# 7segdmux.net
KiCad netlist of a schematic drawn in EAGLE
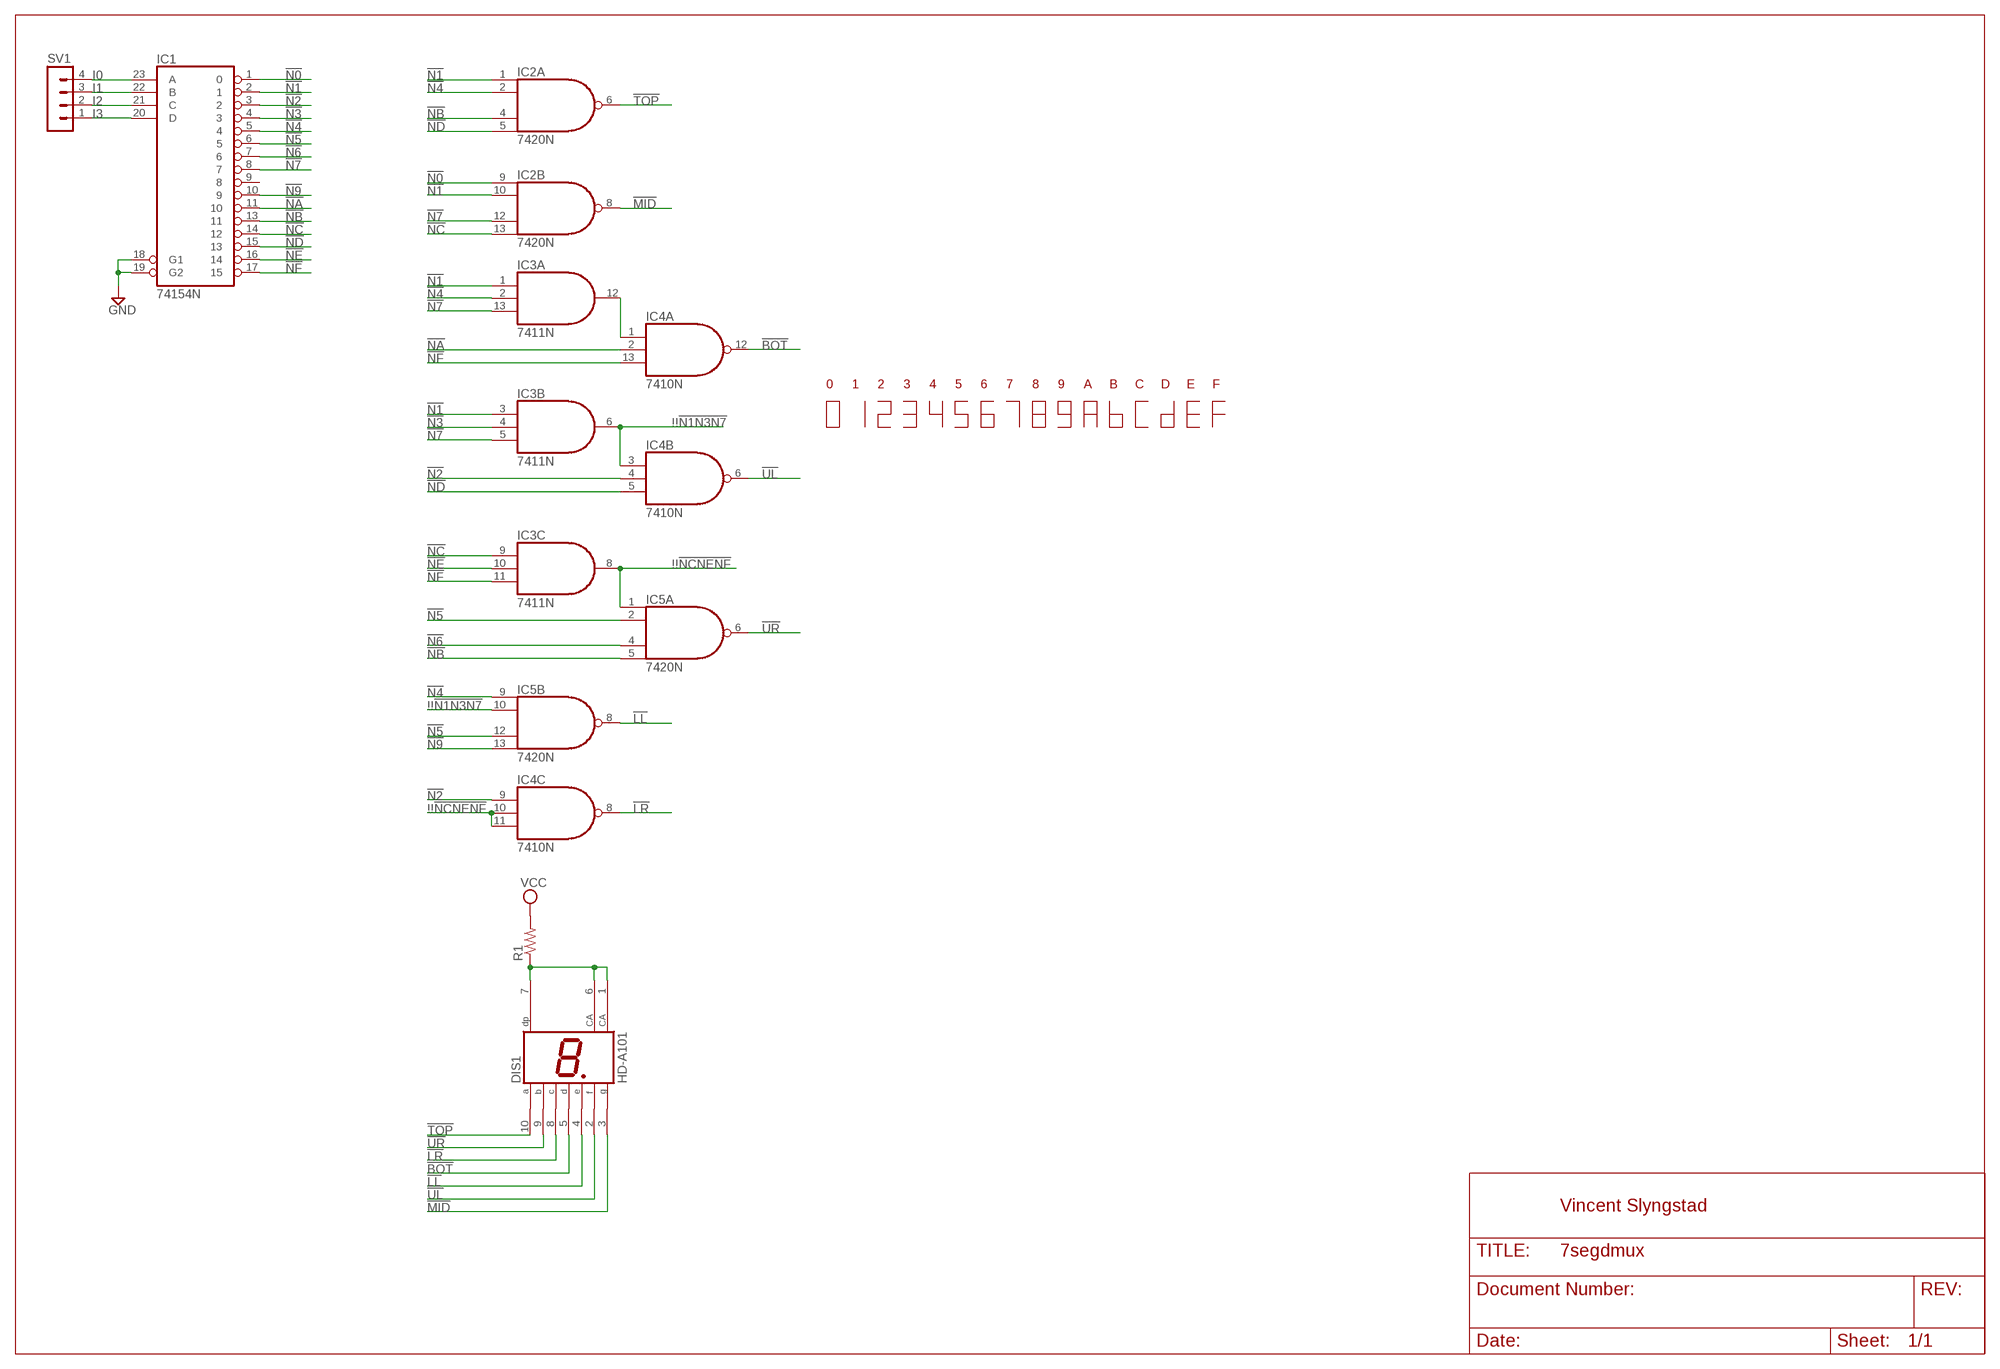
[diagram p0: schematic, sheet 1]

(export (version "E")
  (design (tool "Eeschema 10.0.6"))
  (components
    (comp (ref "DIS1")
      (value "HD-A101")
      (footprint "eagle-import:HDSP-A")
      (libsource (lib "eagle-import") (part "HD-A101"))
    )
    (comp (ref "IC1")
      (value "74154N")
      (footprint "eagle-import:DIL24-6")
      (libsource (lib "eagle-import") (part "74154N"))
    )
    (comp (ref "IC2")
      (value "7420N")
      (footprint "eagle-import:DIL14")
      (libsource (lib "eagle-import") (part "7420NS"))
    )
    (comp (ref "IC3")
      (value "7411N")
      (footprint "eagle-import:DIL14")
      (libsource (lib "eagle-import") (part "7411NS"))
    )
    (comp (ref "IC4")
      (value "7410N")
      (footprint "eagle-import:DIL14")
      (libsource (lib "eagle-import") (part "7410N"))
    )
    (comp (ref "IC5")
      (value "7420N")
      (footprint "eagle-import:DIL14")
      (libsource (lib "eagle-import") (part "7420NS"))
    )
    (comp (ref "R1")
      (value "R-US_0207/10")
      (footprint "eagle-import:0207_10")
      (libsource (lib "eagle-import") (part "R-US_0207/10"))
    )
    (comp (ref "SV1")
      (value "MA04-1")
      (footprint "eagle-import:MA04-1")
      (libsource (lib "eagle-import") (part "MA04-1"))
    )
  )
  (nets
    (net (code "1") (name "/I0") (class "Default")
      (node (ref "IC1") (pin "23") (pinfunction "A_23") (pintype "input"))
      (node (ref "SV1") (pin "4") (pinfunction "4_4") (pintype "passive"))
    )
    (net (code "2") (name "/I1") (class "Default")
      (node (ref "IC1") (pin "22") (pinfunction "B_22") (pintype "input"))
      (node (ref "SV1") (pin "3") (pinfunction "3_3") (pintype "passive"))
    )
    (net (code "3") (name "/I2") (class "Default")
      (node (ref "IC1") (pin "21") (pinfunction "C_21") (pintype "input"))
      (node (ref "SV1") (pin "2") (pinfunction "2_2") (pintype "passive"))
    )
    (net (code "4") (name "/I3") (class "Default")
      (node (ref "IC1") (pin "20") (pinfunction "D_20") (pintype "input"))
      (node (ref "SV1") (pin "1") (pinfunction "1_1") (pintype "passive"))
    )
    (net (code "5") (name "/~{BOT}") (class "Default")
      (node (ref "DIS1") (pin "5") (pinfunction "D_5") (pintype "passive"))
      (node (ref "IC4") (pin "12") (pinfunction "O_12") (pintype "output"))
    )
    (net (code "6") (name "/~{LL}") (class "Default")
      (node (ref "DIS1") (pin "4") (pinfunction "E_4") (pintype "passive"))
      (node (ref "IC5") (pin "8") (pinfunction "O_8") (pintype "output"))
    )
    (net (code "7") (name "/~{LR}") (class "Default")
      (node (ref "DIS1") (pin "8") (pinfunction "C_8") (pintype "passive"))
      (node (ref "IC4") (pin "8") (pinfunction "O_8") (pintype "output"))
    )
    (net (code "8") (name "/~{MID}") (class "Default")
      (node (ref "DIS1") (pin "3") (pinfunction "G_3") (pintype "passive"))
      (node (ref "IC2") (pin "8") (pinfunction "O_8") (pintype "output"))
    )
    (net (code "9") (name "/~{N0}") (class "Default")
      (node (ref "IC1") (pin "1") (pinfunction "0_1") (pintype "output"))
      (node (ref "IC2") (pin "9") (pinfunction "I0_9") (pintype "input"))
    )
    (net (code "10") (name "/~{N1}") (class "Default")
      (node (ref "IC1") (pin "2") (pinfunction "1_2") (pintype "output"))
      (node (ref "IC2") (pin "1") (pinfunction "I0_1") (pintype "input"))
      (node (ref "IC2") (pin "10") (pinfunction "I1_10") (pintype "input"))
      (node (ref "IC3") (pin "1") (pinfunction "I0_1") (pintype "input"))
      (node (ref "IC3") (pin "3") (pinfunction "I0_3") (pintype "input"))
    )
    (net (code "11") (name "/~{N2}") (class "Default")
      (node (ref "IC1") (pin "3") (pinfunction "2_3") (pintype "output"))
      (node (ref "IC4") (pin "4") (pinfunction "I1_4") (pintype "input"))
      (node (ref "IC4") (pin "9") (pinfunction "I0_9") (pintype "input"))
    )
    (net (code "12") (name "/~{N3}") (class "Default")
      (node (ref "IC1") (pin "4") (pinfunction "3_4") (pintype "output"))
      (node (ref "IC3") (pin "4") (pinfunction "I1_4") (pintype "input"))
    )
    (net (code "13") (name "/~{N4}") (class "Default")
      (node (ref "IC1") (pin "5") (pinfunction "4_5") (pintype "output"))
      (node (ref "IC2") (pin "2") (pinfunction "I1_2") (pintype "input"))
      (node (ref "IC3") (pin "2") (pinfunction "I1_2") (pintype "input"))
      (node (ref "IC5") (pin "9") (pinfunction "I0_9") (pintype "input"))
    )
    (net (code "14") (name "/~{N5}") (class "Default")
      (node (ref "IC1") (pin "6") (pinfunction "5_6") (pintype "output"))
      (node (ref "IC5") (pin "12") (pinfunction "I2_12") (pintype "input"))
      (node (ref "IC5") (pin "2") (pinfunction "I1_2") (pintype "input"))
    )
    (net (code "15") (name "/~{N6}") (class "Default")
      (node (ref "IC1") (pin "7") (pinfunction "6_7") (pintype "output"))
      (node (ref "IC5") (pin "4") (pinfunction "I2_4") (pintype "input"))
    )
    (net (code "16") (name "/~{N7}") (class "Default")
      (node (ref "IC1") (pin "8") (pinfunction "7_8") (pintype "output"))
      (node (ref "IC2") (pin "12") (pinfunction "I2_12") (pintype "input"))
      (node (ref "IC3") (pin "13") (pinfunction "I2_13") (pintype "input"))
      (node (ref "IC3") (pin "5") (pinfunction "I2_5") (pintype "input"))
    )
    (net (code "17") (name "/~{N9}") (class "Default")
      (node (ref "IC1") (pin "10") (pinfunction "9_10") (pintype "output"))
      (node (ref "IC5") (pin "13") (pinfunction "I3_13") (pintype "input"))
    )
    (net (code "18") (name "/~{NA}") (class "Default")
      (node (ref "IC1") (pin "11") (pinfunction "10_11") (pintype "output"))
      (node (ref "IC4") (pin "2") (pinfunction "I1_2") (pintype "input"))
    )
    (net (code "19") (name "/~{NB}") (class "Default")
      (node (ref "IC1") (pin "13") (pinfunction "11_13") (pintype "output"))
      (node (ref "IC2") (pin "4") (pinfunction "I2_4") (pintype "input"))
      (node (ref "IC5") (pin "5") (pinfunction "I3_5") (pintype "input"))
    )
    (net (code "20") (name "/~{NC}") (class "Default")
      (node (ref "IC1") (pin "14") (pinfunction "12_14") (pintype "output"))
      (node (ref "IC2") (pin "13") (pinfunction "I3_13") (pintype "input"))
      (node (ref "IC3") (pin "9") (pinfunction "I0_9") (pintype "input"))
    )
    (net (code "21") (name "/~{ND}") (class "Default")
      (node (ref "IC1") (pin "15") (pinfunction "13_15") (pintype "output"))
      (node (ref "IC2") (pin "5") (pinfunction "I3_5") (pintype "input"))
      (node (ref "IC4") (pin "5") (pinfunction "I2_5") (pintype "input"))
    )
    (net (code "22") (name "/~{NE}") (class "Default")
      (node (ref "IC1") (pin "16") (pinfunction "14_16") (pintype "output"))
      (node (ref "IC3") (pin "10") (pinfunction "I1_10") (pintype "input"))
    )
    (net (code "23") (name "/~{NF}") (class "Default")
      (node (ref "IC1") (pin "17") (pinfunction "15_17") (pintype "output"))
      (node (ref "IC3") (pin "11") (pinfunction "I2_11") (pintype "input"))
      (node (ref "IC4") (pin "13") (pinfunction "I2_13") (pintype "input"))
    )
    (net (code "24") (name "/~{TOP}") (class "Default")
      (node (ref "DIS1") (pin "10") (pinfunction "A_10") (pintype "passive"))
      (node (ref "IC2") (pin "6") (pinfunction "O_6") (pintype "output"))
    )
    (net (code "25") (name "/~{UL}") (class "Default")
      (node (ref "DIS1") (pin "2") (pinfunction "F_2") (pintype "passive"))
      (node (ref "IC4") (pin "6") (pinfunction "O_6") (pintype "output"))
    )
    (net (code "26") (name "/~{UR}") (class "Default")
      (node (ref "DIS1") (pin "9") (pinfunction "B_9") (pintype "passive"))
      (node (ref "IC5") (pin "6") (pinfunction "O_6") (pintype "output"))
    )
    (net (code "27") (name "/~~{N1N3N7}") (class "Default")
      (node (ref "IC3") (pin "6") (pinfunction "O_6") (pintype "output"))
      (node (ref "IC4") (pin "3") (pinfunction "I0_3") (pintype "input"))
      (node (ref "IC5") (pin "10") (pinfunction "I1_10") (pintype "input"))
    )
    (net (code "28") (name "/~~{NCNENF}") (class "Default")
      (node (ref "IC3") (pin "8") (pinfunction "O_8") (pintype "output"))
      (node (ref "IC4") (pin "10") (pinfunction "I1_10") (pintype "input"))
      (node (ref "IC4") (pin "11") (pinfunction "I2_11") (pintype "input"))
      (node (ref "IC5") (pin "1") (pinfunction "I0_1") (pintype "input"))
    )
    (net (code "29") (name "GND") (class "Default")
      (node (ref "IC1") (pin "18") (pinfunction "G1_18") (pintype "input"))
      (node (ref "IC1") (pin "19") (pinfunction "G2_19") (pintype "input"))
    )
    (net (code "30") (name "Net-(DIS1-DP)") (class "Default")
      (node (ref "DIS1") (pin "1") (pinfunction "CA_1") (pintype "passive"))
      (node (ref "DIS1") (pin "6") (pinfunction "CA_6") (pintype "passive"))
      (node (ref "DIS1") (pin "7") (pinfunction "DP_7") (pintype "passive"))
      (node (ref "R1") (pin "1") (pinfunction "1_1") (pintype "passive"))
    )
    (net (code "31") (name "Net-(IC3A-O)") (class "Default")
      (node (ref "IC3") (pin "12") (pinfunction "O_12") (pintype "output"))
      (node (ref "IC4") (pin "1") (pinfunction "I0_1") (pintype "input"))
    )
    (net (code "32") (name "VCC") (class "Default")
      (node (ref "R1") (pin "2") (pinfunction "2_2") (pintype "passive"))
    )
    (net (code "33") (name "unconnected-(IC1A-8-Pad9)") (class "Default")
      (node (ref "IC1") (pin "9") (pinfunction "8_9") (pintype "output"))
    )
  )
)
